# CLASS_AB.net
KiCad netlist of a schematic drawn in Altium Designer
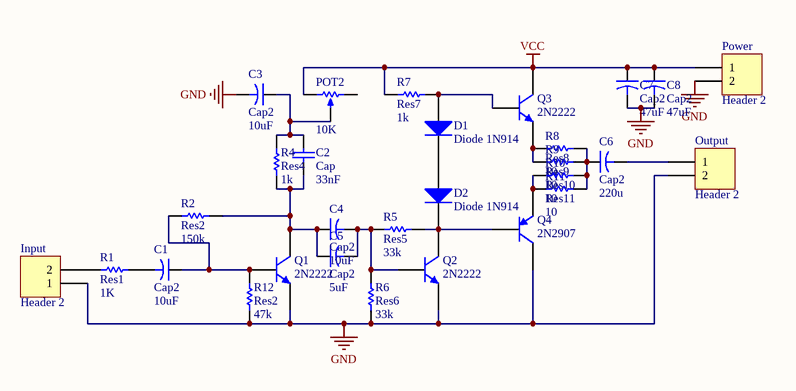
[diagram p0: CLASS_AB.SchDoc]

(export (version "E")
  (design (tool "Eeschema 10.0.6"))
  (components
    (comp (ref "C1")
      (value "Cap2")
      (footprint "CAPR5-4X5")
      (description "Capacitor")
      (fields (field (name "ALTIUM_VALUE") "10uF") (field (name "PUBLISHER") "Altium Limited"))
      (libsource (lib "Miscellaneous Devices") (part "Cap2"))
    )
    (comp (ref "C2")
      (value "Cap")
      (footprint "RAD-0.3")
      (description "Capacitor")
      (fields (field (name "ALTIUM_VALUE") "33nF") (field (name "PUBLISHER") "Altium Limited"))
      (libsource (lib "Miscellaneous Devices") (part "Cap"))
    )
    (comp (ref "C3")
      (value "Cap2")
      (footprint "CAPR5-4X5")
      (description "Capacitor")
      (fields (field (name "ALTIUM_VALUE") "10uF") (field (name "PUBLISHER") "Altium Limited"))
      (libsource (lib "Miscellaneous Devices") (part "Cap2"))
    )
    (comp (ref "C4")
      (value "Cap2")
      (footprint "CAPR5-4X5")
      (description "Capacitor")
      (fields (field (name "ALTIUM_VALUE") "10uF") (field (name "PUBLISHER") "Altium Limited"))
      (libsource (lib "Miscellaneous Devices") (part "Cap2"))
    )
    (comp (ref "C5")
      (value "Cap2")
      (footprint "CAPR5-4X5")
      (description "Capacitor")
      (fields (field (name "ALTIUM_VALUE") "5uF") (field (name "PUBLISHER") "Altium Limited"))
      (libsource (lib "Miscellaneous Devices") (part "Cap2"))
    )
    (comp (ref "C6")
      (value "Cap2")
      (footprint "CAPR5-4X5")
      (description "Capacitor")
      (fields (field (name "ALTIUM_VALUE") "220u") (field (name "PUBLISHER") "Altium Limited"))
      (libsource (lib "Miscellaneous Devices") (part "Cap2"))
    )
    (comp (ref "C7")
      (value "Cap2")
      (footprint "CAPR5-4X5")
      (description "Capacitor")
      (fields (field (name "ALTIUM_VALUE") "47uF") (field (name "PUBLISHER") "Altium Limited"))
      (libsource (lib "Miscellaneous Devices") (part "Cap2"))
    )
    (comp (ref "C8")
      (value "Cap2")
      (footprint "CAPR5-4X5")
      (description "Capacitor")
      (fields (field (name "ALTIUM_VALUE") "47uF") (field (name "PUBLISHER") "Altium Limited"))
      (libsource (lib "Miscellaneous Devices") (part "Cap2"))
    )
    (comp (ref "D1")
      (value "Diode 1N914")
      (footprint "DO-35")
      (description "High Conductance Fast Diode")
      (fields (field (name "PUBLISHER") "Altium Limited"))
      (libsource (lib "Miscellaneous Devices") (part "Diode 1N914"))
    )
    (comp (ref "D2")
      (value "Diode 1N914")
      (footprint "DO-35")
      (description "High Conductance Fast Diode")
      (fields (field (name "PUBLISHER") "Altium Limited"))
      (libsource (lib "Miscellaneous Devices") (part "Diode 1N914"))
    )
    (comp (ref "Input")
      (value "Header 2")
      (footprint "HDR1X2")
      (description "Header, 2-Pin")
      (fields (field (name "PUBLISHER") "Altium Limited"))
      (libsource (lib "Miscellaneous Connectors") (part "Header 2"))
    )
    (comp (ref "Output")
      (value "Header 2")
      (footprint "HDR1X2")
      (description "Header, 2-Pin")
      (fields (field (name "PUBLISHER") "Altium Limited"))
      (libsource (lib "") (part "Header 2_1"))
    )
    (comp (ref "POT2")
      (value "10K")
      (footprint "POT inline wide")
      (description "Potentiometer")
      (fields (field (name "Comment") "RPot_1") (field (name "PUBLISHER") "Altium Limited"))
      (libsource (lib "ECE LIB new") (part "RPot_3"))
    )
    (comp (ref "Power")
      (value "Header 2")
      (footprint "HDR1X2")
      (description "Header, 2-Pin")
      (fields (field (name "PUBLISHER") "Altium Limited"))
      (libsource (lib "") (part "Header 2_1"))
    )
    (comp (ref "Q1")
      (value "2N2222")
      (footprint "TO-92A")
      (description "NPN General Purpose Amplifier")
      (fields (field (name "PUBLISHER") "Altium Limited"))
      (libsource (lib "Miscellaneous Devices") (part "2N3904"))
    )
    (comp (ref "Q2")
      (value "2N2222")
      (footprint "TO-92A")
      (description "NPN General Purpose Amplifier")
      (fields (field (name "PUBLISHER") "Altium Limited"))
      (libsource (lib "Miscellaneous Devices") (part "2N3904"))
    )
    (comp (ref "Q3")
      (value "2N2222")
      (footprint "TO-92A")
      (description "NPN General Purpose Amplifier")
      (fields (field (name "PUBLISHER") "Altium Limited"))
      (libsource (lib "Miscellaneous Devices") (part "2N3904"))
    )
    (comp (ref "Q4")
      (value "2N2907")
      (footprint "TO-92A")
      (description "PNP General Purpose Amplifier")
      (fields (field (name "PUBLISHER") "Altium Limited"))
      (libsource (lib "Miscellaneous Devices") (part "2N3906"))
    )
    (comp (ref "R1")
      (value "Res1")
      (footprint "AXIAL-0.3")
      (description "Resistor")
      (fields (field (name "ALTIUM_VALUE") "1K") (field (name "PUBLISHER") "Altium Limited"))
      (libsource (lib "Miscellaneous Devices") (part "Res1"))
    )
    (comp (ref "R2")
      (value "Res2")
      (footprint "AXIAL-0.3")
      (description "Resistor")
      (fields (field (name "ALTIUM_VALUE") "150k") (field (name "PUBLISHER") "Altium Limited"))
      (libsource (lib "Miscellaneous Devices") (part "Res1"))
    )
    (comp (ref "R4")
      (value "Res4")
      (footprint "AXIAL-0.3")
      (description "Resistor")
      (fields (field (name "ALTIUM_VALUE") "1k") (field (name "PUBLISHER") "Altium Limited"))
      (libsource (lib "Miscellaneous Devices") (part "Res1"))
    )
    (comp (ref "R5")
      (value "Res5")
      (footprint "AXIAL-0.3")
      (description "Resistor")
      (fields (field (name "ALTIUM_VALUE") "33k") (field (name "PUBLISHER") "Altium Limited"))
      (libsource (lib "Miscellaneous Devices") (part "Res1"))
    )
    (comp (ref "R6")
      (value "Res6")
      (footprint "AXIAL-0.3")
      (description "Resistor")
      (fields (field (name "ALTIUM_VALUE") "33k") (field (name "PUBLISHER") "Altium Limited"))
      (libsource (lib "Miscellaneous Devices") (part "Res1"))
    )
    (comp (ref "R7")
      (value "Res7")
      (footprint "AXIAL-0.3")
      (description "Resistor")
      (fields (field (name "ALTIUM_VALUE") "1k") (field (name "PUBLISHER") "Altium Limited"))
      (libsource (lib "Miscellaneous Devices") (part "Res1"))
    )
    (comp (ref "R8")
      (value "Res8")
      (footprint "AXIAL-0.3")
      (description "Resistor")
      (fields (field (name "ALTIUM_VALUE") "10") (field (name "PUBLISHER") "Altium Limited"))
      (libsource (lib "Miscellaneous Devices") (part "Res1"))
    )
    (comp (ref "R9")
      (value "Res9")
      (footprint "AXIAL-0.3")
      (description "Resistor")
      (fields (field (name "ALTIUM_VALUE") "10") (field (name "PUBLISHER") "Altium Limited"))
      (libsource (lib "Miscellaneous Devices") (part "Res1"))
    )
    (comp (ref "R10")
      (value "Res10")
      (footprint "AXIAL-0.3")
      (description "Resistor")
      (fields (field (name "ALTIUM_VALUE") "10") (field (name "PUBLISHER") "Altium Limited"))
      (libsource (lib "Miscellaneous Devices") (part "Res1"))
    )
    (comp (ref "R11")
      (value "Res11")
      (footprint "AXIAL-0.3")
      (description "Resistor")
      (fields (field (name "ALTIUM_VALUE") "10") (field (name "PUBLISHER") "Altium Limited"))
      (libsource (lib "Miscellaneous Devices") (part "Res1"))
    )
    (comp (ref "R12")
      (value "Res2")
      (footprint "AXIAL-0.3")
      (description "Resistor")
      (fields (field (name "ALTIUM_VALUE") "47k") (field (name "PUBLISHER") "Altium Limited"))
      (libsource (lib "Miscellaneous Devices") (part "Res1"))
    )
  )
  (nets
    (net (code "1") (name "GND") (class "Default")
      (node (ref "C3") (pin "2") (pinfunction "2_2") (pintype "passive"))
      (node (ref "C7") (pin "2") (pinfunction "2_2") (pintype "passive"))
      (node (ref "C8") (pin "2") (pinfunction "2_2") (pintype "passive"))
      (node (ref "Input") (pin "1") (pinfunction "1_1") (pintype "passive"))
      (node (ref "Output") (pin "2") (pinfunction "2_2") (pintype "passive"))
      (node (ref "Power") (pin "2") (pinfunction "2_2") (pintype "passive"))
      (node (ref "Q1") (pin "1") (pinfunction "E_1") (pintype "passive"))
      (node (ref "Q2") (pin "1") (pinfunction "E_1") (pintype "passive"))
      (node (ref "Q4") (pin "3") (pinfunction "C_3") (pintype "passive"))
      (node (ref "R12") (pin "2") (pinfunction "2_2") (pintype "passive"))
      (node (ref "R6") (pin "1") (pinfunction "1_1") (pintype "passive"))
    )
    (net (code "2") (name "Net-(C1-Pad2)") (class "Default")
      (node (ref "C1") (pin "2") (pinfunction "2_2") (pintype "passive"))
      (node (ref "R1") (pin "2") (pinfunction "2_2") (pintype "passive"))
    )
    (net (code "3") (name "Net-(C6-Pad1)") (class "Default")
      (node (ref "C6") (pin "1") (pinfunction "1_1") (pintype "passive"))
      (node (ref "R10") (pin "1") (pinfunction "1_1") (pintype "passive"))
      (node (ref "R11") (pin "1") (pinfunction "1_1") (pintype "passive"))
      (node (ref "R8") (pin "1") (pinfunction "1_1") (pintype "passive"))
      (node (ref "R9") (pin "1") (pinfunction "1_1") (pintype "passive"))
    )
    (net (code "4") (name "Net-(C6-Pad2)") (class "Default")
      (node (ref "C6") (pin "2") (pinfunction "2_2") (pintype "passive"))
      (node (ref "Output") (pin "1") (pinfunction "1_1") (pintype "passive"))
    )
    (net (code "5") (name "Net-(D1-A)") (class "Default")
      (node (ref "D1") (pin "1") (pinfunction "A_1") (pintype "passive"))
      (node (ref "Q3") (pin "2") (pinfunction "B_2") (pintype "passive"))
      (node (ref "R7") (pin "1") (pinfunction "1_1") (pintype "passive"))
    )
    (net (code "6") (name "Net-(D1-K)") (class "Default")
      (node (ref "D1") (pin "2") (pinfunction "K_2") (pintype "passive"))
      (node (ref "D2") (pin "1") (pinfunction "A_1") (pintype "passive"))
    )
    (net (code "7") (name "Net-(D2-K)") (class "Default")
      (node (ref "D2") (pin "2") (pinfunction "K_2") (pintype "passive"))
      (node (ref "Q2") (pin "3") (pinfunction "C_3") (pintype "passive"))
      (node (ref "Q4") (pin "2") (pinfunction "B_2") (pintype "passive"))
      (node (ref "R5") (pin "1") (pinfunction "1_1") (pintype "passive"))
    )
    (net (code "8") (name "Net-(Input-Pad2)") (class "Default")
      (node (ref "Input") (pin "2") (pinfunction "2_2") (pintype "passive"))
      (node (ref "R1") (pin "1") (pinfunction "1_1") (pintype "passive"))
    )
    (net (code "9") (name "Net-(POT2-TAP)") (class "Default")
      (node (ref "C2") (pin "2") (pinfunction "2_2") (pintype "passive"))
      (node (ref "C3") (pin "1") (pinfunction "1_1") (pintype "passive"))
      (node (ref "POT2") (pin "2") (pinfunction "TAP_2") (pintype "passive"))
      (node (ref "R4") (pin "1") (pinfunction "1_1") (pintype "passive"))
    )
    (net (code "10") (name "Net-(Q1-B)") (class "Default")
      (node (ref "C1") (pin "1") (pinfunction "1_1") (pintype "passive"))
      (node (ref "Q1") (pin "2") (pinfunction "B_2") (pintype "passive"))
      (node (ref "R12") (pin "1") (pinfunction "1_1") (pintype "passive"))
      (node (ref "R2") (pin "2") (pinfunction "2_2") (pintype "passive"))
    )
    (net (code "11") (name "Net-(Q1-C)") (class "Default")
      (node (ref "C2") (pin "1") (pinfunction "1_1") (pintype "passive"))
      (node (ref "C4") (pin "1") (pinfunction "1_1") (pintype "passive"))
      (node (ref "C5") (pin "1") (pinfunction "1_1") (pintype "passive"))
      (node (ref "Q1") (pin "3") (pinfunction "C_3") (pintype "passive"))
      (node (ref "R2") (pin "1") (pinfunction "1_1") (pintype "passive"))
      (node (ref "R4") (pin "2") (pinfunction "2_2") (pintype "passive"))
    )
    (net (code "12") (name "Net-(Q2-B)") (class "Default")
      (node (ref "C4") (pin "2") (pinfunction "2_2") (pintype "passive"))
      (node (ref "C5") (pin "2") (pinfunction "2_2") (pintype "passive"))
      (node (ref "Q2") (pin "2") (pinfunction "B_2") (pintype "passive"))
      (node (ref "R5") (pin "2") (pinfunction "2_2") (pintype "passive"))
      (node (ref "R6") (pin "2") (pinfunction "2_2") (pintype "passive"))
    )
    (net (code "13") (name "Net-(Q3-E)") (class "Default")
      (node (ref "Q3") (pin "1") (pinfunction "E_1") (pintype "passive"))
      (node (ref "R8") (pin "2") (pinfunction "2_2") (pintype "passive"))
      (node (ref "R9") (pin "2") (pinfunction "2_2") (pintype "passive"))
    )
    (net (code "14") (name "Net-(Q4-E)") (class "Default")
      (node (ref "Q4") (pin "1") (pinfunction "E_1") (pintype "passive"))
      (node (ref "R10") (pin "2") (pinfunction "2_2") (pintype "passive"))
      (node (ref "R11") (pin "2") (pinfunction "2_2") (pintype "passive"))
    )
    (net (code "15") (name "VCC") (class "Default")
      (node (ref "C7") (pin "1") (pinfunction "1_1") (pintype "passive"))
      (node (ref "C8") (pin "1") (pinfunction "1_1") (pintype "passive"))
      (node (ref "POT2") (pin "1") (pinfunction "TOP_1") (pintype "passive"))
      (node (ref "Power") (pin "1") (pinfunction "1_1") (pintype "passive"))
      (node (ref "Q3") (pin "3") (pinfunction "C_3") (pintype "passive"))
      (node (ref "R7") (pin "2") (pinfunction "2_2") (pintype "passive"))
    )
    (net (code "16") (name "unconnected-(POT2-BOT-Pad3)") (class "Default")
      (node (ref "POT2") (pin "3") (pinfunction "BOT_3") (pintype "passive"))
    )
  )
)
